# weather_shield.net
KiCad netlist of a schematic drawn in EAGLE
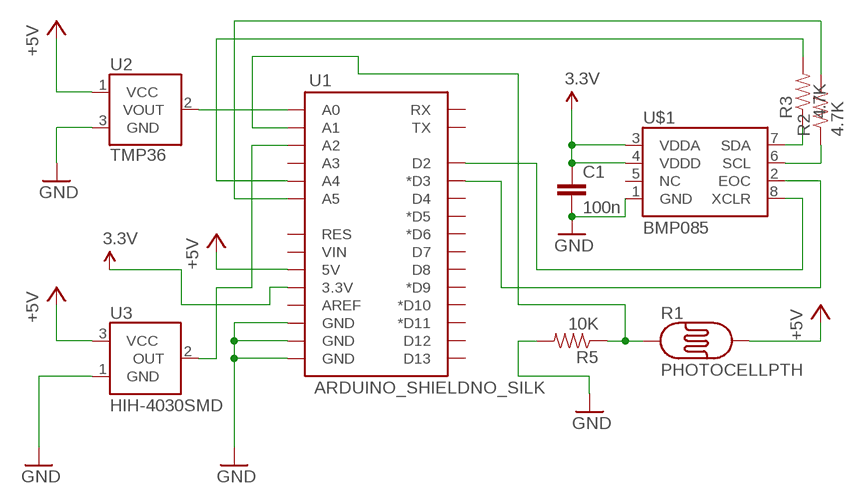
[diagram p0: schematic, sheet 1]

(export (version "E")
  (design (tool "Eeschema 10.0.6"))
  (components
    (comp (ref "C1")
      (value "100n")
      (footprint "eagle-import:1206")
      (libsource (lib "eagle-import") (part "CAP1206"))
    )
    (comp (ref "R1")
      (value "PHOTOCELLPTH")
      (footprint "eagle-import:PHOTOCELL")
      (libsource (lib "eagle-import") (part "PHOTOCELLPTH"))
    )
    (comp (ref "R2")
      (value "4.7K")
      (footprint "eagle-import:1206")
      (libsource (lib "eagle-import") (part "RESISTOR1206"))
    )
    (comp (ref "R3")
      (value "4.7K")
      (footprint "eagle-import:1206")
      (libsource (lib "eagle-import") (part "RESISTOR1206"))
    )
    (comp (ref "R5")
      (value "10K")
      (footprint "eagle-import:1206")
      (libsource (lib "eagle-import") (part "RESISTOR1206"))
    )
    (comp (ref "U$1")
      (value "BMP085")
      (footprint "eagle-import:BMP085")
      (libsource (lib "eagle-import") (part "BMP085"))
    )
    (comp (ref "U1")
      (value "ARDUINO_SHIELDNO_SILK")
      (footprint "eagle-import:DUEMILANOVE_VIAS")
      (libsource (lib "eagle-import") (part "ARDUINO_SHIELDNO_SILK"))
    )
    (comp (ref "U2")
      (value "TMP36")
      (footprint "eagle-import:TO-92")
      (libsource (lib "eagle-import") (part "TMP36GT9"))
    )
    (comp (ref "U3")
      (value "HIH-4030SMD")
      (footprint "eagle-import:HIH-4030")
      (libsource (lib "eagle-import") (part "HIH-4030SMD"))
    )
  )
  (nets
    (net (code "1") (name "+5V") (class "Default")
      (node (ref "R1") (pin "2") (pinfunction "P$2_2") (pintype "bidirectional"))
      (node (ref "U1") (pin "5V") (pinfunction "5V_5V") (pintype "bidirectional"))
      (node (ref "U2") (pin "1") (pinfunction "VCC_1") (pintype "bidirectional"))
      (node (ref "U3") (pin "3") (pinfunction "VCC_3") (pintype "bidirectional"))
    )
    (net (code "2") (name "3.3V") (class "Default")
      (node (ref "C1") (pin "1") (pinfunction "1_1") (pintype "passive"))
      (node (ref "U$1") (pin "3") (pinfunction "VDDA_3") (pintype "power_in"))
      (node (ref "U$1") (pin "4") (pinfunction "VDDD_4") (pintype "power_in"))
      (node (ref "U1") (pin "3.3V") (pinfunction "3.3V_3.3V") (pintype "bidirectional"))
    )
    (net (code "3") (name "GND") (class "Default")
      (node (ref "C1") (pin "2") (pinfunction "2_2") (pintype "passive"))
      (node (ref "R5") (pin "2") (pinfunction "2_2") (pintype "passive"))
      (node (ref "U$1") (pin "1") (pinfunction "GND_1") (pintype "power_in"))
      (node (ref "U1") (pin "GND@0") (pinfunction "GND_GND@0") (pintype "bidirectional"))
      (node (ref "U1") (pin "GND@1") (pinfunction "GND_GND@1") (pintype "bidirectional"))
      (node (ref "U1") (pin "GND@2") (pinfunction "GND_GND@2") (pintype "bidirectional"))
      (node (ref "U2") (pin "3") (pinfunction "GND_3") (pintype "bidirectional"))
      (node (ref "U3") (pin "1") (pinfunction "GND_1") (pintype "bidirectional"))
    )
    (net (code "4") (name "Net-(R1-P$1)") (class "Default")
      (node (ref "R1") (pin "1") (pinfunction "P$1_1") (pintype "bidirectional"))
      (node (ref "R5") (pin "1") (pinfunction "1_1") (pintype "passive"))
      (node (ref "U1") (pin "A1") (pinfunction "A1_A1") (pintype "bidirectional"))
    )
    (net (code "5") (name "Net-(R2-Pad2)") (class "Default")
      (node (ref "R2") (pin "2") (pinfunction "2_2") (pintype "passive"))
      (node (ref "U1") (pin "A5") (pinfunction "A5_A5") (pintype "bidirectional"))
    )
    (net (code "6") (name "Net-(R3-Pad2)") (class "Default")
      (node (ref "R3") (pin "2") (pinfunction "2_2") (pintype "passive"))
      (node (ref "U1") (pin "A4") (pinfunction "A4_A4") (pintype "bidirectional"))
    )
    (net (code "7") (name "Net-(U$1-EOC)") (class "Default")
      (node (ref "U$1") (pin "2") (pinfunction "EOC_2") (pintype "output"))
      (node (ref "U1") (pin "D3") (pinfunction "*D3_D3") (pintype "bidirectional"))
    )
    (net (code "8") (name "Net-(U$1-SCL)") (class "Default")
      (node (ref "R2") (pin "1") (pinfunction "1_1") (pintype "passive"))
      (node (ref "U$1") (pin "6") (pinfunction "SCL_6") (pintype "input"))
    )
    (net (code "9") (name "Net-(U$1-SDA)") (class "Default")
      (node (ref "R3") (pin "1") (pinfunction "1_1") (pintype "passive"))
      (node (ref "U$1") (pin "7") (pinfunction "SDA_7") (pintype "bidirectional"))
    )
    (net (code "10") (name "Net-(U$1-XCLR)") (class "Default")
      (node (ref "U$1") (pin "8") (pinfunction "XCLR_8") (pintype "input"))
      (node (ref "U1") (pin "D2") (pinfunction "D2_D2") (pintype "bidirectional"))
    )
    (net (code "11") (name "Net-(U2-VOUT)") (class "Default")
      (node (ref "U1") (pin "A0") (pinfunction "A0_A0") (pintype "bidirectional"))
      (node (ref "U2") (pin "2") (pinfunction "VOUT_2") (pintype "bidirectional"))
    )
    (net (code "12") (name "Net-(U3-OUT)") (class "Default")
      (node (ref "U1") (pin "A2") (pinfunction "A2_A2") (pintype "bidirectional"))
      (node (ref "U3") (pin "2") (pinfunction "OUT_2") (pintype "bidirectional"))
    )
    (net (code "13") (name "unconnected-(U$1-NC-Pad5)") (class "Default")
      (node (ref "U$1") (pin "5") (pinfunction "NC_5") (pintype "bidirectional"))
    )
    (net (code "14") (name "unconnected-(U1-*D5-PadD5)") (class "Default")
      (node (ref "U1") (pin "D5") (pinfunction "*D5_D5") (pintype "bidirectional"))
    )
    (net (code "15") (name "unconnected-(U1-*D6-PadD6)") (class "Default")
      (node (ref "U1") (pin "D6") (pinfunction "*D6_D6") (pintype "bidirectional"))
    )
    (net (code "16") (name "unconnected-(U1-*D9-PadD9)") (class "Default")
      (node (ref "U1") (pin "D9") (pinfunction "*D9_D9") (pintype "bidirectional"))
    )
    (net (code "17") (name "unconnected-(U1-*D10-PadD10)") (class "Default")
      (node (ref "U1") (pin "D10") (pinfunction "*D10_D10") (pintype "bidirectional"))
    )
    (net (code "18") (name "unconnected-(U1-*D11-PadD11)") (class "Default")
      (node (ref "U1") (pin "D11") (pinfunction "*D11_D11") (pintype "bidirectional"))
    )
    (net (code "19") (name "unconnected-(U1-PadA3)") (class "Default")
      (node (ref "U1") (pin "A3") (pinfunction "A3_A3") (pintype "bidirectional"))
    )
    (net (code "20") (name "unconnected-(U1-PadAREF)") (class "Default")
      (node (ref "U1") (pin "AREF") (pinfunction "AREF_AREF") (pintype "bidirectional"))
    )
    (net (code "21") (name "unconnected-(U1-PadD4)") (class "Default")
      (node (ref "U1") (pin "D4") (pinfunction "D4_D4") (pintype "bidirectional"))
    )
    (net (code "22") (name "unconnected-(U1-PadD7)") (class "Default")
      (node (ref "U1") (pin "D7") (pinfunction "D7_D7") (pintype "bidirectional"))
    )
    (net (code "23") (name "unconnected-(U1-PadD8)") (class "Default")
      (node (ref "U1") (pin "D8") (pinfunction "D8_D8") (pintype "bidirectional"))
    )
    (net (code "24") (name "unconnected-(U1-PadD12)") (class "Default")
      (node (ref "U1") (pin "D12") (pinfunction "D12_D12") (pintype "bidirectional"))
    )
    (net (code "25") (name "unconnected-(U1-PadD13)") (class "Default")
      (node (ref "U1") (pin "D13") (pinfunction "D13_D13") (pintype "bidirectional"))
    )
    (net (code "26") (name "unconnected-(U1-PadRES)") (class "Default")
      (node (ref "U1") (pin "RES") (pinfunction "RES_RES") (pintype "bidirectional"))
    )
    (net (code "27") (name "unconnected-(U1-PadRX)") (class "Default")
      (node (ref "U1") (pin "RX") (pinfunction "RX_RX") (pintype "bidirectional"))
    )
    (net (code "28") (name "unconnected-(U1-PadTX)") (class "Default")
      (node (ref "U1") (pin "TX") (pinfunction "TX_TX") (pintype "bidirectional"))
    )
    (net (code "29") (name "unconnected-(U1-PadVIN)") (class "Default")
      (node (ref "U1") (pin "VIN") (pinfunction "VIN_VIN") (pintype "bidirectional"))
    )
  )
)
